# CAN_Interface.net
KiCad netlist of a schematic drawn in Altium Designer
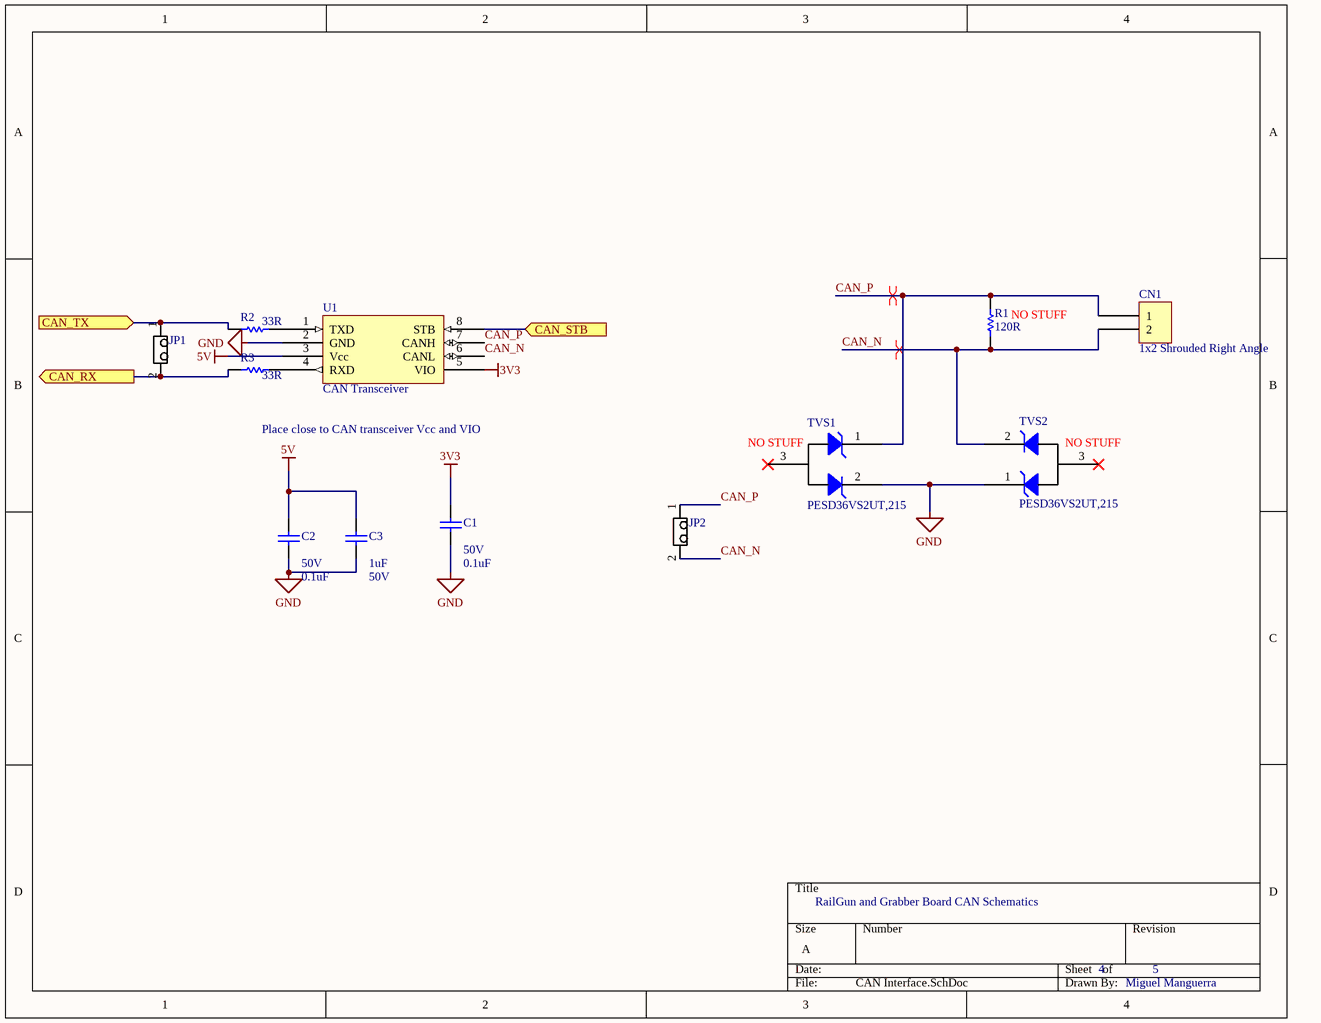
[diagram p0: CAN Interface.SchDoc]

(export (version "E")
  (design (tool "Eeschema 10.0.6"))
  (components
    (comp (ref "C1")
      (value "CL10B104JB8NNNC")
      (footprint "FP-CL10-0_1-MFG")
      (description "CAP CER 0.1UF 50V X7R 0603")
      (fields
        (field (name "TOLERANCE") "5%")
        (field (name "VOLTAGE") "50V")
        (field (name "CAPACITANCE") "0.1uF")
      )
      (libsource (lib "AUVIC") (part "CAP-NP-2"))
    )
    (comp (ref "C2")
      (value "CL10B104JB8NNNC")
      (footprint "FP-CL10-0_1-MFG")
      (description "CAP CER 0.1UF 50V X7R 0603")
      (fields
        (field (name "TOLERANCE") "5%")
        (field (name "VOLTAGE") "50V")
        (field (name "CAPACITANCE") "0.1uF")
      )
      (libsource (lib "AUVIC") (part "CAP-NP-2"))
    )
    (comp (ref "C3")
      (value "CL21B105KBFNNNG")
      (footprint "0803 CAP")
      (description "SAMSUNG ELECTRO-MECHANICS - CL21B105KBFNNNG - MLCC CAPACITORS")
      (fields
        (field (name "TOLERANCE") "10%")
        (field (name "CAPACITANCE") "1uF")
        (field (name "VOLTAGE") "50V")
      )
      (libsource (lib "AUVIC") (part "Symbol"))
    )
    (comp (ref "CN1")
      (value "1x2 Shrouded Right Angle")
      (footprint "2X1 Female Header")
      (description "02 MTE HDR SRRA LATCH")
      (libsource (lib "AUVIC") (part "1x2 Shrouded Right Angle"))
    )
    (comp (ref "JP1")
      (value "1x2 Male Header")
      (footprint "2X1 Males Header")
      (fields
        (field (name "SOURCE") "AUVic_Schematic_Library_Connectors.SchLib")
        (field (name "MADE BY") "Andy Bates")
      )
      (libsource (lib "AUVIC") (part "1x2 Male Header"))
    )
    (comp (ref "JP2")
      (value "1x2 Male Header")
      (footprint "2X1 Males Header")
      (fields
        (field (name "SOURCE") "AUVic_Schematic_Library_Connectors.SchLib")
        (field (name "MADE BY") "Andy Bates")
      )
      (libsource (lib "AUVIC") (part "1x2 Male Header"))
    )
    (comp (ref "R1")
      (value "120R")
      (footprint "RESC1608X55X25LL10T15")
      (description "Res Thick Film 0603 120 Ohm 1% 0.1W(1/10W) ±100ppm/C Epoxy SMD T/R")
      (fields (field (name "TOLERANCE") "1%"))
      (libsource (lib "AUVIC") (part "RES-2"))
    )
    (comp (ref "R2")
      (value "33R")
      (footprint "RESC1608X55X25LL10T15")
      (description "Res Thick Film 0603 33 Ohm 1% 1/10W +/-100ppm/ßC Molded SMD Paper T/R")
      (fields (field (name "TOLERANCE") "1%"))
      (libsource (lib "AUVIC") (part "RES-2"))
    )
    (comp (ref "R3")
      (value "33R")
      (footprint "RESC1608X55X25LL10T15")
      (description "Res Thick Film 0603 33 Ohm 1% 1/10W +/-100ppm/ßC Molded SMD Paper T/R")
      (fields (field (name "TOLERANCE") "1%"))
      (libsource (lib "AUVIC") (part "RES-2"))
    )
    (comp (ref "TVS1")
      (value "PESD36VS2UT,215")
      (footprint "SOT95P245X110-3N")
      (description "TVS DIODE 36V 60V SOT23")
      (fields
        (field (name "CREATED BY") "Miguel Manguerra")
        (field (name "SOURCE") "AUVic_Schematic_Library_Diodes.SchLib")
      )
      (libsource (lib "AUVIC") (part "PESD36VS2UT,215"))
    )
    (comp (ref "TVS2")
      (value "PESD36VS2UT,215")
      (footprint "SOT95P245X110-3N")
      (description "TVS DIODE 36V 60V SOT23")
      (fields
        (field (name "CREATED BY") "Miguel Manguerra")
        (field (name "SOURCE") "AUVic_Schematic_Library_Diodes.SchLib")
      )
      (libsource (lib "AUVIC") (part "PESD36VS2UT,215"))
    )
    (comp (ref "U1")
      (value "CAN Transceiver")
      (footprint "8-SOIC")
      (description "1/1 Transceiver Half CANbus 8-SO")
      (libsource (lib "AUVIC") (part "CAN Transceiver"))
    )
  )
  (nets
    (net (code "1") (name "/CAN_N") (class "Default")
      (node (ref "CN1") (pin "2") (pinfunction "2_2") (pintype "passive"))
      (node (ref "JP2") (pin "2") (pinfunction "2_2") (pintype "passive"))
      (node (ref "R1") (pin "2") (pinfunction "2_2") (pintype "passive"))
      (node (ref "TVS2") (pin "2") (pinfunction "Cathode_2_2") (pintype "passive"))
      (node (ref "U1") (pin "6") (pinfunction "CANL_6") (pintype "bidirectional"))
    )
    (net (code "2") (name "/CAN_P") (class "Default")
      (node (ref "CN1") (pin "1") (pinfunction "1_1") (pintype "passive"))
      (node (ref "JP2") (pin "1") (pinfunction "1_1") (pintype "passive"))
      (node (ref "R1") (pin "1") (pinfunction "1_1") (pintype "passive"))
      (node (ref "TVS1") (pin "1") (pinfunction "Cathode_1_1") (pintype "passive"))
      (node (ref "U1") (pin "7") (pinfunction "CANH_7") (pintype "bidirectional"))
    )
    (net (code "3") (name "/CAN_RX") (class "Default")
      (node (ref "JP1") (pin "2") (pinfunction "2_2") (pintype "passive"))
      (node (ref "R3") (pin "1") (pinfunction "1_1") (pintype "passive"))
    )
    (net (code "4") (name "/CAN_STB") (class "Default")
      (node (ref "U1") (pin "8") (pinfunction "STB_8") (pintype "input"))
    )
    (net (code "5") (name "/CAN_TX") (class "Default")
      (node (ref "JP1") (pin "1") (pinfunction "1_1") (pintype "passive"))
      (node (ref "R2") (pin "1") (pinfunction "1_1") (pintype "passive"))
    )
    (net (code "6") (name "3V3") (class "Default")
      (node (ref "C1") (pin "1") (pinfunction "1_1") (pintype "passive"))
      (node (ref "U1") (pin "5") (pinfunction "VIO_5") (pintype "passive"))
    )
    (net (code "7") (name "5V") (class "Default")
      (node (ref "C2") (pin "1") (pinfunction "1_1") (pintype "passive"))
      (node (ref "C3") (pin "1") (pinfunction "1_1") (pintype "passive"))
      (node (ref "U1") (pin "3") (pinfunction "Vcc_3") (pintype "power_in"))
    )
    (net (code "8") (name "GND") (class "Default")
      (node (ref "C1") (pin "2") (pinfunction "2_2") (pintype "passive"))
      (node (ref "C2") (pin "2") (pinfunction "2_2") (pintype "passive"))
      (node (ref "C3") (pin "2") (pinfunction "2_2") (pintype "passive"))
      (node (ref "TVS1") (pin "2") (pinfunction "Cathode_2_2") (pintype "passive"))
      (node (ref "TVS2") (pin "1") (pinfunction "Cathode_1_1") (pintype "passive"))
      (node (ref "U1") (pin "2") (pinfunction "GND_2") (pintype "power_in"))
    )
    (net (code "9") (name "Net-(U1-RXD)") (class "Default")
      (node (ref "R3") (pin "2") (pinfunction "2_2") (pintype "passive"))
      (node (ref "U1") (pin "4") (pinfunction "RXD_4") (pintype "output"))
    )
    (net (code "10") (name "Net-(U1-TXD)") (class "Default")
      (node (ref "R2") (pin "2") (pinfunction "2_2") (pintype "passive"))
      (node (ref "U1") (pin "1") (pinfunction "TXD_1") (pintype "input"))
    )
    (net (code "11") (name "unconnected-(TVS1-Common_Anode-Pad3)") (class "Default")
      (node (ref "TVS1") (pin "3") (pinfunction "Common_Anode_3") (pintype "passive"))
    )
    (net (code "12") (name "unconnected-(TVS2-Common_Anode-Pad3)") (class "Default")
      (node (ref "TVS2") (pin "3") (pinfunction "Common_Anode_3") (pintype "passive"))
    )
  )
)
